# BBB_Headers.net
KiCad netlist of a schematic drawn in Altium Designer
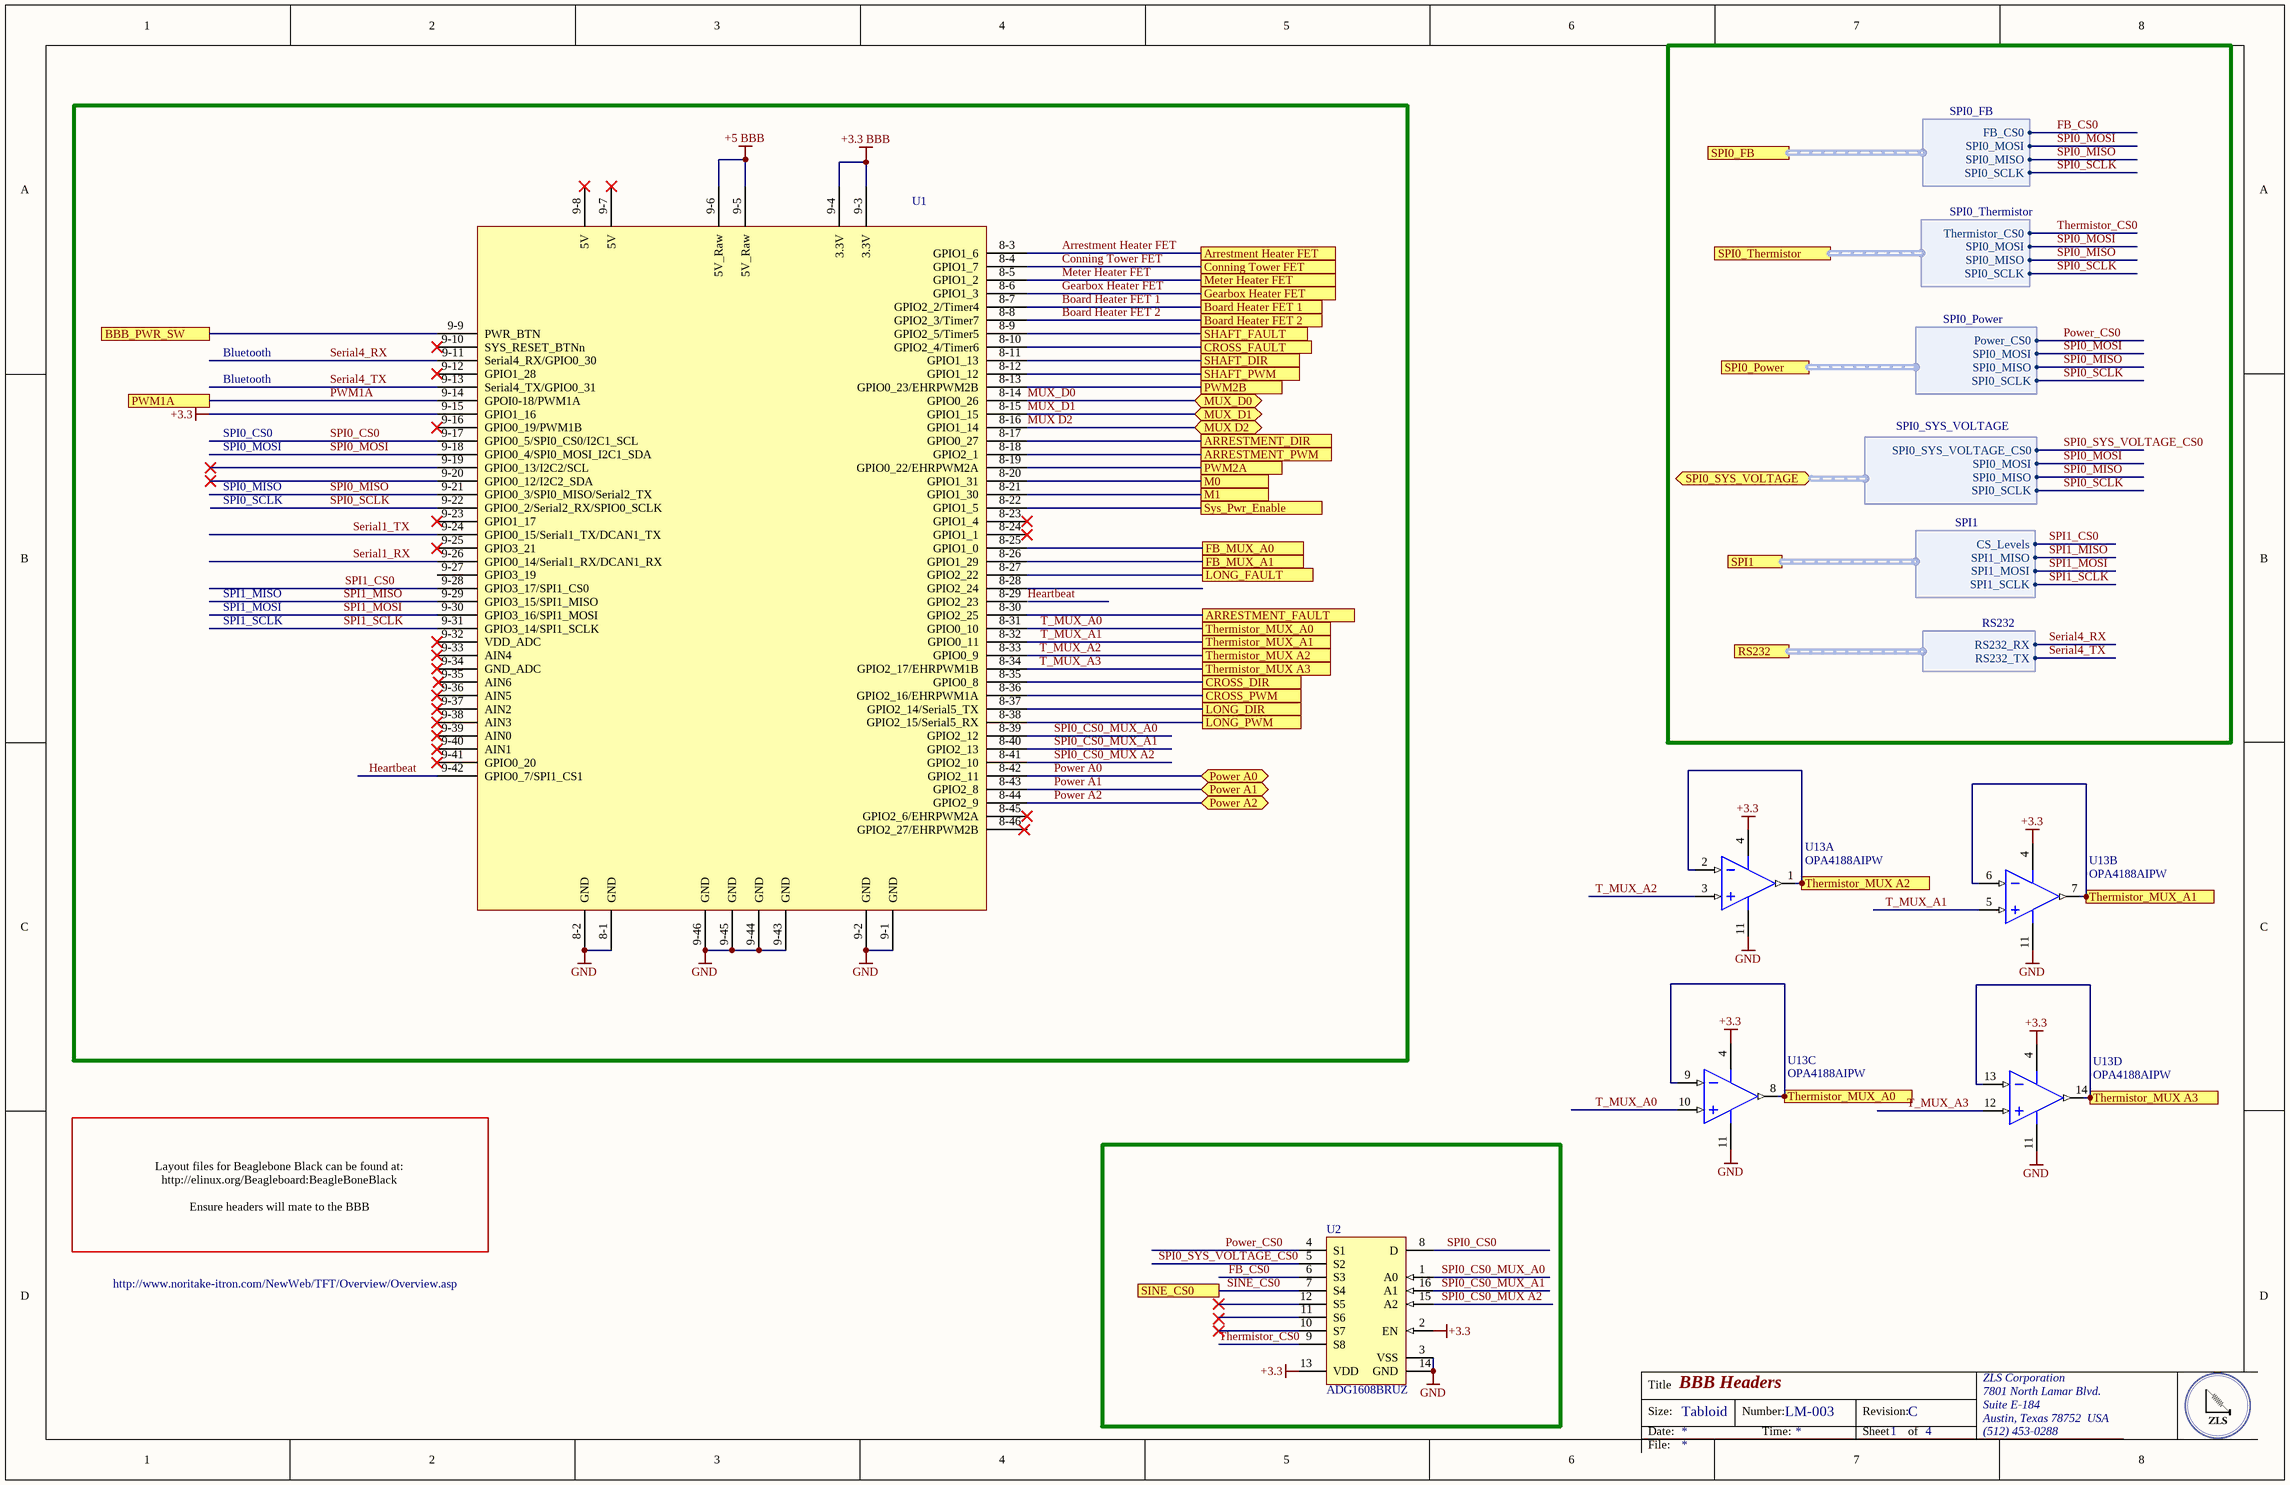
[diagram p0: BBB Headers.SchDoc]

(export (version "E")
  (design (tool "Eeschema 10.0.6"))
  (components
    (comp (ref "U1")
      (value "BBB Header x 2")
      (footprint "Beaglebone Black Thru")
      (description "Beaglebone Black Header")
      (fields
        (field (name "MANUFACTURER") "Samtec Inc.")
        (field (name "MANUFACTURER PART NUMBER") "SSW-123-03-G-D")
      )
      (libsource (lib "ZLS_Schematic_lib") (part "Beaglebone_Black"))
    )
    (comp (ref "U2")
      (value "ADG1608BRUZ")
      (footprint "ADI-RU-16_M")
      (description "4.5 Ohm Ron, 8-Channel +/-5 V,+12 V, +5 V and +3.3 V Multiplexer, 16-pin SOP (RU-16), Tube")
      (fields (field (name "MANUFACTURER") "Analog Devices Inc.") (field (name "BASE PART NUMBER") "ADG1608"))
      (libsource (lib "Altium Content Vault") (part "CMP-0793-00136-1"))
    )
    (comp (ref "U13")
      (value "OPA4188AIPW")
      (footprint "PW0014A_N")
      (fields (field (name "MANUFACTURER") "Texas Instruments"))
      (libsource (lib "Altium Content Vault") (part "TI-OPA4188-PW14"))
    )
  )
  (nets
    (net (code "7") (name "+3.3") (class "Default")
      (node (ref "U1") (pin "9-15") (pinfunction "GPIO1_16_9-15") (pintype "passive"))
      (node (ref "U13") (pin "4") (pinfunction "V+_4") (pintype "power_in"))
      (node (ref "U2") (pin "13") (pinfunction "VDD_13") (pintype "power_in"))
      (node (ref "U2") (pin "2") (pinfunction "EN_2") (pintype "input"))
    )
    (net (code "8") (name "+3.3 BBB") (class "Default")
      (node (ref "U1") (pin "9-3") (pinfunction "3.3V_9-3") (pintype "passive"))
      (node (ref "U1") (pin "9-4") (pinfunction "3.3V_9-4") (pintype "passive"))
    )
    (net (code "9") (name "+5 BBB") (class "Default")
      (node (ref "U1") (pin "9-5") (pinfunction "5V_Raw_9-5") (pintype "passive"))
      (node (ref "U1") (pin "9-6") (pinfunction "5V_Raw_9-6") (pintype "passive"))
    )
    (net (code "10") (name "/ARRESTMENT_DIR") (class "Default")
      (node (ref "U1") (pin "8-17") (pinfunction "GPIO0_27_8-17") (pintype "passive"))
    )
    (net (code "11") (name "/ARRESTMENT_FAULT") (class "Default")
      (node (ref "U1") (pin "8-30") (pinfunction "GPIO2_25_8-30") (pintype "passive"))
    )
    (net (code "12") (name "/ARRESTMENT_PWM") (class "Default")
      (node (ref "U1") (pin "8-18") (pinfunction "GPIO2_1_8-18") (pintype "passive"))
    )
    (net (code "13") (name "/Arrestment Heater FET") (class "Default")
      (node (ref "U1") (pin "8-3") (pinfunction "GPIO1_6_8-3") (pintype "passive"))
    )
    (net (code "14") (name "/BBB_PWR_SW") (class "Default")
      (node (ref "U1") (pin "9-9") (pinfunction "PWR_BTN_9-9") (pintype "passive"))
    )
    (net (code "15") (name "/Board Heater FET 1") (class "Default")
      (node (ref "U1") (pin "8-7") (pinfunction "GPIO2_2/Timer4_8-7") (pintype "passive"))
    )
    (net (code "16") (name "/Board Heater FET 2") (class "Default")
      (node (ref "U1") (pin "8-8") (pinfunction "GPIO2_3/Timer7_8-8") (pintype "passive"))
    )
    (net (code "17") (name "/CROSS_DIR") (class "Default")
      (node (ref "U1") (pin "8-35") (pinfunction "GPIO0_8_8-35") (pintype "passive"))
    )
    (net (code "18") (name "/CROSS_FAULT") (class "Default")
      (node (ref "U1") (pin "8-10") (pinfunction "GPIO2_4/Timer6_8-10") (pintype "passive"))
    )
    (net (code "19") (name "/CROSS_PWM") (class "Default")
      (node (ref "U1") (pin "8-36") (pinfunction "GPIO2_16/EHRPWM1A_8-36") (pintype "passive"))
    )
    (net (code "20") (name "/Conning Tower FET") (class "Default")
      (node (ref "U1") (pin "8-4") (pinfunction "GPIO1_7_8-4") (pintype "passive"))
    )
    (net (code "21") (name "/FB_CS0") (class "Default")
      (node (ref "U2") (pin "6") (pinfunction "S3_6") (pintype "passive"))
    )
    (net (code "22") (name "/FB_MUX_A0") (class "Default")
      (node (ref "U1") (pin "8-25") (pinfunction "GPIO1_0_8-25") (pintype "passive"))
    )
    (net (code "23") (name "/FB_MUX_A1") (class "Default")
      (node (ref "U1") (pin "8-26") (pinfunction "GPIO1_29_8-26") (pintype "passive"))
    )
    (net (code "24") (name "/Gearbox Heater FET") (class "Default")
      (node (ref "U1") (pin "8-6") (pinfunction "GPIO1_3_8-6") (pintype "passive"))
    )
    (net (code "25") (name "/Heartbeat") (class "Default")
      (node (ref "U1") (pin "8-29") (pinfunction "GPIO2_23_8-29") (pintype "passive"))
      (node (ref "U1") (pin "9-42") (pinfunction "GPIO0_7/SPI1_CS1_9-42") (pintype "passive"))
    )
    (net (code "26") (name "/LONG_DIR") (class "Default")
      (node (ref "U1") (pin "8-37") (pinfunction "GPIO2_14/Serial5_TX_8-37") (pintype "passive"))
    )
    (net (code "27") (name "/LONG_FAULT") (class "Default")
      (node (ref "U1") (pin "8-27") (pinfunction "GPIO2_22_8-27") (pintype "passive"))
    )
    (net (code "28") (name "/LONG_PWM") (class "Default")
      (node (ref "U1") (pin "8-38") (pinfunction "GPIO2_15/Serial5_RX_8-38") (pintype "passive"))
    )
    (net (code "29") (name "/M0") (class "Default")
      (node (ref "U1") (pin "8-20") (pinfunction "GPIO1_31_8-20") (pintype "passive"))
    )
    (net (code "30") (name "/M1") (class "Default")
      (node (ref "U1") (pin "8-21") (pinfunction "GPIO1_30_8-21") (pintype "passive"))
    )
    (net (code "31") (name "/MUX D2") (class "Default")
      (node (ref "U1") (pin "8-16") (pinfunction "GPIO1_14_8-16") (pintype "passive"))
    )
    (net (code "32") (name "/MUX_D0") (class "Default")
      (node (ref "U1") (pin "8-14") (pinfunction "GPIO0_26_8-14") (pintype "passive"))
    )
    (net (code "33") (name "/MUX_D1") (class "Default")
      (node (ref "U1") (pin "8-15") (pinfunction "GPIO1_15_8-15") (pintype "passive"))
    )
    (net (code "34") (name "/Meter Heater FET") (class "Default")
      (node (ref "U1") (pin "8-5") (pinfunction "GPIO1_2_8-5") (pintype "passive"))
    )
    (net (code "35") (name "/PWM1A") (class "Default")
      (node (ref "U1") (pin "9-14") (pinfunction "GPOI0-18/PWM1A_9-14") (pintype "passive"))
    )
    (net (code "36") (name "/PWM2A") (class "Default")
      (node (ref "U1") (pin "8-19") (pinfunction "GPIO0_22/EHRPWM2A_8-19") (pintype "passive"))
    )
    (net (code "37") (name "/PWM2B") (class "Default")
      (node (ref "U1") (pin "8-13") (pinfunction "GPIO0_23/EHRPWM2B_8-13") (pintype "passive"))
    )
    (net (code "38") (name "/Power A0") (class "Default")
      (node (ref "U1") (pin "8-42") (pinfunction "GPIO2_11_8-42") (pintype "passive"))
    )
    (net (code "39") (name "/Power A1") (class "Default")
      (node (ref "U1") (pin "8-43") (pinfunction "GPIO2_8_8-43") (pintype "passive"))
    )
    (net (code "40") (name "/Power A2") (class "Default")
      (node (ref "U1") (pin "8-44") (pinfunction "GPIO2_9_8-44") (pintype "passive"))
    )
    (net (code "41") (name "/Power_CS0") (class "Default")
      (node (ref "U2") (pin "4") (pinfunction "S1_4") (pintype "passive"))
    )
    (net (code "42") (name "/SHAFT_DIR") (class "Default")
      (node (ref "U1") (pin "8-11") (pinfunction "GPIO1_13_8-11") (pintype "passive"))
    )
    (net (code "43") (name "/SHAFT_FAULT") (class "Default")
      (node (ref "U1") (pin "8-9") (pinfunction "GPIO2_5/Timer5_8-9") (pintype "passive"))
    )
    (net (code "44") (name "/SHAFT_PWM") (class "Default")
      (node (ref "U1") (pin "8-12") (pinfunction "GPIO1_12_8-12") (pintype "passive"))
    )
    (net (code "45") (name "/SINE_CS0") (class "Default")
      (node (ref "U2") (pin "7") (pinfunction "S4_7") (pintype "passive"))
    )
    (net (code "46") (name "/SPI0_CS0") (class "Default")
      (node (ref "U1") (pin "9-17") (pinfunction "GPIO0_5/SPI0_CS0/I2C1_SCL_9-17") (pintype "passive"))
      (node (ref "U2") (pin "8") (pinfunction "D_8") (pintype "passive"))
    )
    (net (code "47") (name "/SPI0_CS0_MUX A2") (class "Default")
      (node (ref "U1") (pin "8-41") (pinfunction "GPIO2_10_8-41") (pintype "passive"))
      (node (ref "U2") (pin "15") (pinfunction "A2_15") (pintype "input"))
    )
    (net (code "48") (name "/SPI0_CS0_MUX_A0") (class "Default")
      (node (ref "U1") (pin "8-39") (pinfunction "GPIO2_12_8-39") (pintype "passive"))
      (node (ref "U2") (pin "1") (pinfunction "A0_1") (pintype "input"))
    )
    (net (code "49") (name "/SPI0_CS0_MUX_A1") (class "Default")
      (node (ref "U1") (pin "8-40") (pinfunction "GPIO2_13_8-40") (pintype "passive"))
      (node (ref "U2") (pin "16") (pinfunction "A1_16") (pintype "input"))
    )
    (net (code "50") (name "/SPI0_MISO") (class "Default")
      (node (ref "U1") (pin "9-21") (pinfunction "GPIO0_3/SPI0_MISO/Serial2_TX_9-21") (pintype "passive"))
    )
    (net (code "51") (name "/SPI0_MOSI") (class "Default")
      (node (ref "U1") (pin "9-18") (pinfunction "GPIO0_4/SPI0_MOSI_I2C1_SDA_9-18") (pintype "passive"))
    )
    (net (code "52") (name "/SPI0_SCLK") (class "Default")
      (node (ref "U1") (pin "9-22") (pinfunction "GPIO0_2/Serial2_RX/SPIO0_SCLK_9-22") (pintype "passive"))
    )
    (net (code "53") (name "/SPI0_SYS_VOLTAGE_CS0") (class "Default")
      (node (ref "U2") (pin "5") (pinfunction "S2_5") (pintype "passive"))
    )
    (net (code "54") (name "/SPI1_CS0") (class "Default")
      (node (ref "U1") (pin "9-28") (pinfunction "GPIO3_17/SPI1_CS0_9-28") (pintype "passive"))
    )
    (net (code "55") (name "/SPI1_MISO") (class "Default")
      (node (ref "U1") (pin "9-29") (pinfunction "GPIO3_15/SPI1_MISO_9-29") (pintype "passive"))
    )
    (net (code "56") (name "/SPI1_MOSI") (class "Default")
      (node (ref "U1") (pin "9-30") (pinfunction "GPIO3_16/SPI1_MOSI_9-30") (pintype "passive"))
    )
    (net (code "57") (name "/SPI1_SCLK") (class "Default")
      (node (ref "U1") (pin "9-31") (pinfunction "GPIO3_14/SPI1_SCLK_9-31") (pintype "passive"))
    )
    (net (code "58") (name "/Serial1_RX") (class "Default")
      (node (ref "U1") (pin "9-26") (pinfunction "GPIO0_14/Serial1_RX/DCAN1_RX_9-26") (pintype "passive"))
    )
    (net (code "59") (name "/Serial1_TX") (class "Default")
      (node (ref "U1") (pin "9-24") (pinfunction "GPIO0_15/Serial1_TX/DCAN1_TX_9-24") (pintype "passive"))
    )
    (net (code "60") (name "/Serial4_RX") (class "Default")
      (node (ref "U1") (pin "9-11") (pinfunction "Serial4_RX/GPIO0_30_9-11") (pintype "passive"))
    )
    (net (code "61") (name "/Serial4_TX") (class "Default")
      (node (ref "U1") (pin "9-13") (pinfunction "Serial4_TX/GPIO0_31_9-13") (pintype "passive"))
    )
    (net (code "62") (name "/Sys_Pwr_Enable") (class "Default")
      (node (ref "U1") (pin "8-22") (pinfunction "GPIO1_5_8-22") (pintype "passive"))
    )
    (net (code "63") (name "/T_MUX_A0") (class "Default")
      (node (ref "U1") (pin "8-31") (pinfunction "GPIO0_10_8-31") (pintype "passive"))
      (node (ref "U13") (pin "10") (pinfunction "IN_C+_10") (pintype "input"))
      (node (ref "U13") (pin "8") (pinfunction "OUT_C_8") (pintype "output"))
      (node (ref "U13") (pin "9") (pinfunction "IN_C-_9") (pintype "input"))
    )
    (net (code "64") (name "/T_MUX_A1") (class "Default")
      (node (ref "U1") (pin "8-32") (pinfunction "GPIO0_11_8-32") (pintype "passive"))
      (node (ref "U13") (pin "5") (pinfunction "IN_B+_5") (pintype "input"))
      (node (ref "U13") (pin "6") (pinfunction "IN_B-_6") (pintype "input"))
      (node (ref "U13") (pin "7") (pinfunction "OUT_B_7") (pintype "output"))
    )
    (net (code "65") (name "/T_MUX_A2") (class "Default")
      (node (ref "U1") (pin "8-33") (pinfunction "GPIO0_9_8-33") (pintype "passive"))
      (node (ref "U13") (pin "1") (pinfunction "OUT_A_1") (pintype "output"))
      (node (ref "U13") (pin "2") (pinfunction "IN_A-_2") (pintype "input"))
      (node (ref "U13") (pin "3") (pinfunction "IN_A+_3") (pintype "input"))
    )
    (net (code "66") (name "/T_MUX_A3") (class "Default")
      (node (ref "U1") (pin "8-34") (pinfunction "GPIO2_17/EHRPWM1B_8-34") (pintype "passive"))
      (node (ref "U13") (pin "12") (pinfunction "IN_D+_12") (pintype "input"))
      (node (ref "U13") (pin "13") (pinfunction "IN_D-_13") (pintype "input"))
      (node (ref "U13") (pin "14") (pinfunction "OUT_D_14") (pintype "output"))
    )
    (net (code "67") (name "/Thermistor_CS0") (class "Default")
      (node (ref "U2") (pin "9") (pinfunction "S8_9") (pintype "passive"))
    )
    (net (code "74") (name "GND") (class "Default")
      (node (ref "U1") (pin "8-1") (pinfunction "GND_8-1") (pintype "passive"))
      (node (ref "U1") (pin "8-2") (pinfunction "GND_8-2") (pintype "passive"))
      (node (ref "U1") (pin "9-1") (pinfunction "GND_9-1") (pintype "passive"))
      (node (ref "U1") (pin "9-2") (pinfunction "GND_9-2") (pintype "passive"))
      (node (ref "U1") (pin "9-43") (pinfunction "GND_9-43") (pintype "passive"))
      (node (ref "U1") (pin "9-44") (pinfunction "GND_9-44") (pintype "passive"))
      (node (ref "U1") (pin "9-45") (pinfunction "GND_9-45") (pintype "passive"))
      (node (ref "U1") (pin "9-46") (pinfunction "GND_9-46") (pintype "passive"))
      (node (ref "U13") (pin "11") (pinfunction "V-_11") (pintype "power_in"))
      (node (ref "U2") (pin "14") (pinfunction "GND_14") (pintype "power_in"))
      (node (ref "U2") (pin "3") (pinfunction "VSS_3") (pintype "power_in"))
    )
    (net (code "75") (name "unconnected-(U1-5V-Pad9-7)") (class "Default")
      (node (ref "U1") (pin "9-7") (pinfunction "5V_9-7") (pintype "passive+no_connect"))
    )
    (net (code "76") (name "unconnected-(U1-5V-Pad9-8)") (class "Default")
      (node (ref "U1") (pin "9-8") (pinfunction "5V_9-8") (pintype "passive+no_connect"))
    )
    (net (code "77") (name "unconnected-(U1-AIN0-Pad9-39)") (class "Default")
      (node (ref "U1") (pin "9-39") (pinfunction "AIN0_9-39") (pintype "passive+no_connect"))
    )
    (net (code "78") (name "unconnected-(U1-AIN1-Pad9-40)") (class "Default")
      (node (ref "U1") (pin "9-40") (pinfunction "AIN1_9-40") (pintype "passive+no_connect"))
    )
    (net (code "79") (name "unconnected-(U1-AIN2-Pad9-37)") (class "Default")
      (node (ref "U1") (pin "9-37") (pinfunction "AIN2_9-37") (pintype "passive+no_connect"))
    )
    (net (code "80") (name "unconnected-(U1-AIN3-Pad9-38)") (class "Default")
      (node (ref "U1") (pin "9-38") (pinfunction "AIN3_9-38") (pintype "passive+no_connect"))
    )
    (net (code "81") (name "unconnected-(U1-AIN4-Pad9-33)") (class "Default")
      (node (ref "U1") (pin "9-33") (pinfunction "AIN4_9-33") (pintype "passive+no_connect"))
    )
    (net (code "82") (name "unconnected-(U1-AIN5-Pad9-36)") (class "Default")
      (node (ref "U1") (pin "9-36") (pinfunction "AIN5_9-36") (pintype "passive+no_connect"))
    )
    (net (code "83") (name "unconnected-(U1-AIN6-Pad9-35)") (class "Default")
      (node (ref "U1") (pin "9-35") (pinfunction "AIN6_9-35") (pintype "passive"))
    )
    (net (code "84") (name "unconnected-(U1-GND_ADC-Pad9-34)") (class "Default")
      (node (ref "U1") (pin "9-34") (pinfunction "GND_ADC_9-34") (pintype "passive+no_connect"))
    )
    (net (code "85") (name "unconnected-(U1-GPIO0_12{slash}I2C2_SDA-Pad9-20)") (class "Default")
      (node (ref "U1") (pin "9-20") (pinfunction "GPIO0_12/I2C2_SDA_9-20") (pintype "passive+no_connect"))
    )
    (net (code "86") (name "unconnected-(U1-GPIO0_13{slash}I2C2{slash}SCL-Pad9-19)") (class "Default")
      (node (ref "U1") (pin "9-19") (pinfunction "GPIO0_13/I2C2/SCL_9-19") (pintype "passive+no_connect"))
    )
    (net (code "87") (name "unconnected-(U1-GPIO0_19{slash}PWM1B-Pad9-16)") (class "Default")
      (node (ref "U1") (pin "9-16") (pinfunction "GPIO0_19/PWM1B_9-16") (pintype "passive+no_connect"))
    )
    (net (code "88") (name "unconnected-(U1-GPIO0_20-Pad9-41)") (class "Default")
      (node (ref "U1") (pin "9-41") (pinfunction "GPIO0_20_9-41") (pintype "passive+no_connect"))
    )
    (net (code "89") (name "unconnected-(U1-GPIO1_1-Pad8-24)") (class "Default")
      (node (ref "U1") (pin "8-24") (pinfunction "GPIO1_1_8-24") (pintype "passive+no_connect"))
    )
    (net (code "90") (name "unconnected-(U1-GPIO1_4-Pad8-23)") (class "Default")
      (node (ref "U1") (pin "8-23") (pinfunction "GPIO1_4_8-23") (pintype "passive+no_connect"))
    )
    (net (code "91") (name "unconnected-(U1-GPIO1_17-Pad9-23)") (class "Default")
      (node (ref "U1") (pin "9-23") (pinfunction "GPIO1_17_9-23") (pintype "passive+no_connect"))
    )
    (net (code "92") (name "unconnected-(U1-GPIO1_28-Pad9-12)") (class "Default")
      (node (ref "U1") (pin "9-12") (pinfunction "GPIO1_28_9-12") (pintype "passive+no_connect"))
    )
    (net (code "93") (name "unconnected-(U1-GPIO2_6{slash}EHRPWM2A-Pad8-45)") (class "Default")
      (node (ref "U1") (pin "8-45") (pinfunction "GPIO2_6/EHRPWM2A_8-45") (pintype "passive+no_connect"))
    )
    (net (code "94") (name "unconnected-(U1-GPIO2_24-Pad8-28)") (class "Default")
      (node (ref "U1") (pin "8-28") (pinfunction "GPIO2_24_8-28") (pintype "passive"))
    )
    (net (code "95") (name "unconnected-(U1-GPIO2_27{slash}EHRPWM2B-Pad8-46)") (class "Default")
      (node (ref "U1") (pin "8-46") (pinfunction "GPIO2_27/EHRPWM2B_8-46") (pintype "passive"))
    )
    (net (code "96") (name "unconnected-(U1-GPIO3_19-Pad9-27)") (class "Default")
      (node (ref "U1") (pin "9-27") (pinfunction "GPIO3_19_9-27") (pintype "passive"))
    )
    (net (code "97") (name "unconnected-(U1-GPIO3_21-Pad9-25)") (class "Default")
      (node (ref "U1") (pin "9-25") (pinfunction "GPIO3_21_9-25") (pintype "passive+no_connect"))
    )
    (net (code "98") (name "unconnected-(U1-SYS_RESET_BTNn-Pad9-10)") (class "Default")
      (node (ref "U1") (pin "9-10") (pinfunction "SYS_RESET_BTNn_9-10") (pintype "passive+no_connect"))
    )
    (net (code "99") (name "unconnected-(U1-VDD_ADC-Pad9-32)") (class "Default")
      (node (ref "U1") (pin "9-32") (pinfunction "VDD_ADC_9-32") (pintype "passive+no_connect"))
    )
    (net (code "100") (name "unconnected-(U2-S5-Pad12)") (class "Default")
      (node (ref "U2") (pin "12") (pinfunction "S5_12") (pintype "passive+no_connect"))
    )
    (net (code "101") (name "unconnected-(U2-S6-Pad11)") (class "Default")
      (node (ref "U2") (pin "11") (pinfunction "S6_11") (pintype "passive"))
    )
    (net (code "102") (name "unconnected-(U2-S7-Pad10)") (class "Default")
      (node (ref "U2") (pin "10") (pinfunction "S7_10") (pintype "passive+no_connect"))
    )
  )
)
